# transmitter_pcb.net
KiCad netlist of a schematic drawn in EAGLE
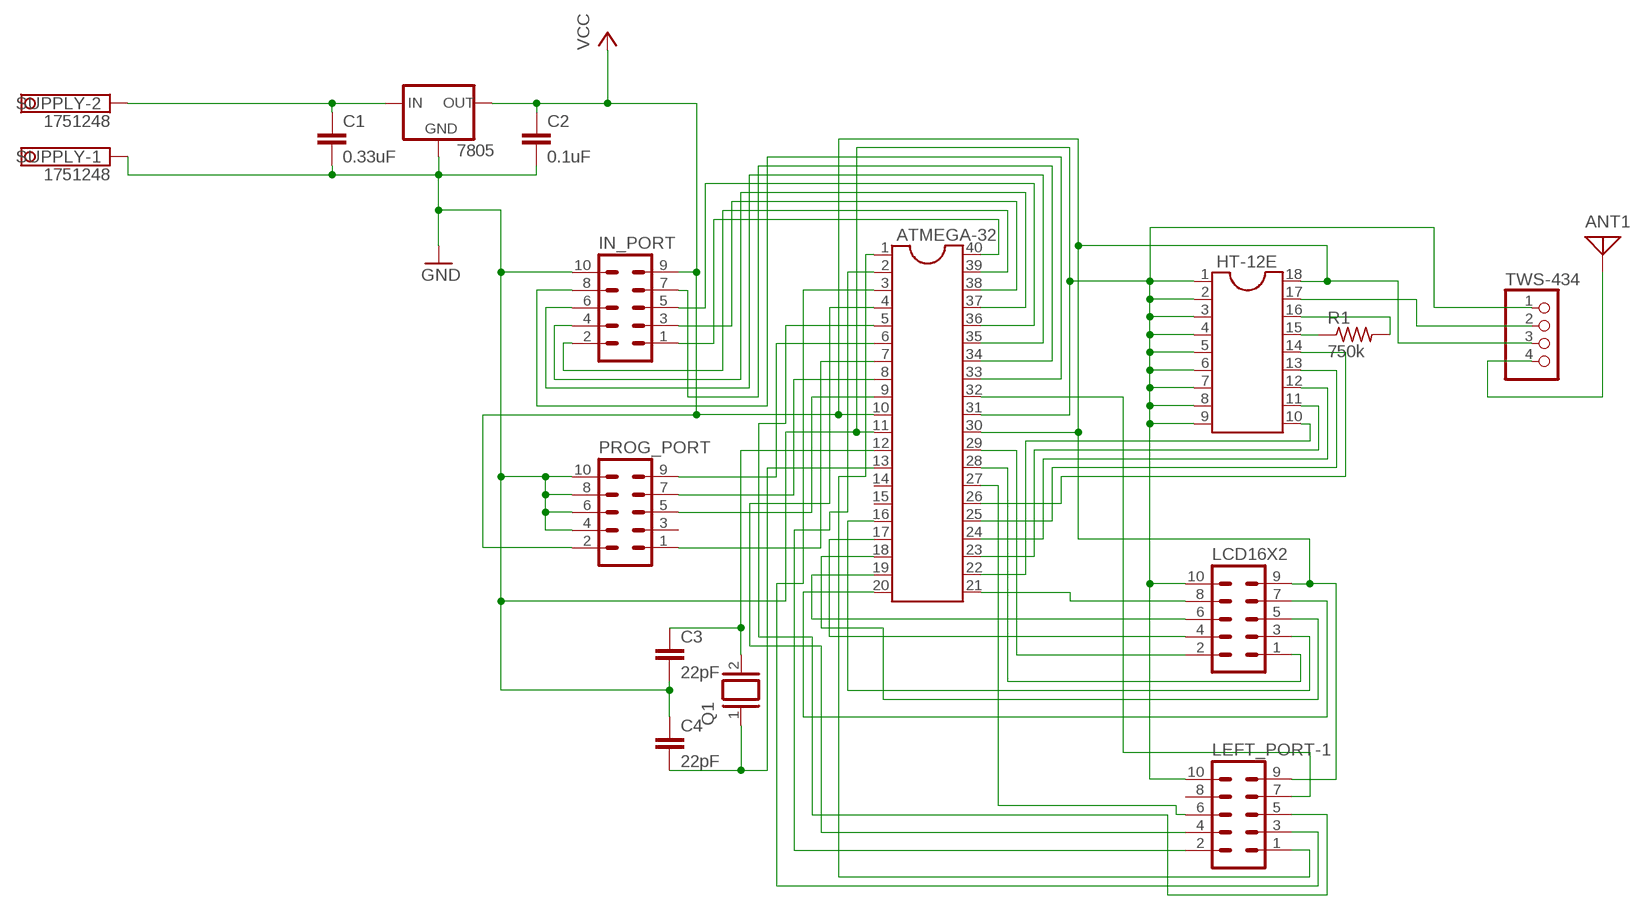
[diagram p0: schematic, sheet 1]

(export (version "E")
  (design (tool "Eeschema 10.0.6"))
  (components
    (comp (ref "7805")
      (value "78XXS")
      (footprint "eagle-import:78XXS")
      (libsource (lib "eagle-import") (part "78XXS"))
    )
    (comp (ref "ANT1")
      (value "ANTENNA")
      (footprint "eagle-import:PAD-01")
      (libsource (lib "eagle-import") (part "ANTENNA"))
    )
    (comp (ref "ATMEGA-32")
      (value "DIL40")
      (footprint "eagle-import:DIL40")
      (libsource (lib "eagle-import") (part "DIL40"))
    )
    (comp (ref "C1")
      (value "0.33uF")
      (footprint "eagle-import:C2.5-2")
      (libsource (lib "eagle-import") (part "C2.5/2"))
    )
    (comp (ref "C2")
      (value "0.1uF")
      (footprint "eagle-import:C2.5-2")
      (libsource (lib "eagle-import") (part "C2.5/2"))
    )
    (comp (ref "C3")
      (value "22pF")
      (footprint "eagle-import:C2.5-2")
      (libsource (lib "eagle-import") (part "C2.5/2"))
    )
    (comp (ref "C4")
      (value "22pF")
      (footprint "eagle-import:C2.5-2")
      (libsource (lib "eagle-import") (part "C2.5/2"))
    )
    (comp (ref "HT-12E")
      (value "DIL18")
      (footprint "eagle-import:DIL18")
      (libsource (lib "eagle-import") (part "DIL18"))
    )
    (comp (ref "IN_PORT")
      (value "ML10")
      (footprint "eagle-import:ML10")
      (libsource (lib "eagle-import") (part "ML10"))
    )
    (comp (ref "LCD16X2")
      (value "ML10")
      (footprint "eagle-import:ML10")
      (libsource (lib "eagle-import") (part "ML10"))
    )
    (comp (ref "LEFT_PORT-1")
      (value "ML10")
      (footprint "eagle-import:ML10")
      (libsource (lib "eagle-import") (part "ML10"))
    )
    (comp (ref "PROG_PORT")
      (value "ML10")
      (footprint "eagle-import:ML10")
      (libsource (lib "eagle-import") (part "ML10"))
    )
    (comp (ref "Q1")
      (value "XTAL/S")
      (footprint "eagle-import:QS")
      (libsource (lib "eagle-import") (part "XTAL/S"))
    )
    (comp (ref "R1")
      (value "750k")
      (footprint "eagle-import:0204_5")
      (libsource (lib "eagle-import") (part "R-US_0204/5"))
    )
    (comp (ref "SUPPLY")
      (value "1751248")
      (footprint "eagle-import:1751248")
      (libsource (lib "eagle-import") (part "1751248"))
    )
    (comp (ref "TWS-434")
      (value "PINHD-1X4")
      (footprint "eagle-import:1X04")
      (libsource (lib "eagle-import") (part "PINHD-1X4"))
    )
  )
  (nets
    (net (code "1") (name "GND") (class "Default")
      (node (ref "7805") (pin "GND") (pinfunction "GND_GND") (pintype "input"))
      (node (ref "ATMEGA-32") (pin "11") (pinfunction "11_11") (pintype "passive"))
      (node (ref "ATMEGA-32") (pin "31") (pinfunction "31_31") (pintype "passive"))
      (node (ref "C1") (pin "2") (pinfunction "2_2") (pintype "passive"))
      (node (ref "C2") (pin "2") (pinfunction "2_2") (pintype "passive"))
      (node (ref "C3") (pin "2") (pinfunction "2_2") (pintype "passive"))
      (node (ref "C4") (pin "1") (pinfunction "1_1") (pintype "passive"))
      (node (ref "HT-12E") (pin "1") (pinfunction "1_1") (pintype "passive"))
      (node (ref "HT-12E") (pin "2") (pinfunction "2_2") (pintype "passive"))
      (node (ref "HT-12E") (pin "3") (pinfunction "3_3") (pintype "passive"))
      (node (ref "HT-12E") (pin "4") (pinfunction "4_4") (pintype "passive"))
      (node (ref "HT-12E") (pin "5") (pinfunction "5_5") (pintype "passive"))
      (node (ref "HT-12E") (pin "6") (pinfunction "6_6") (pintype "passive"))
      (node (ref "HT-12E") (pin "7") (pinfunction "7_7") (pintype "passive"))
      (node (ref "HT-12E") (pin "8") (pinfunction "8_8") (pintype "passive"))
      (node (ref "HT-12E") (pin "9") (pinfunction "9_9") (pintype "passive"))
      (node (ref "IN_PORT") (pin "10") (pinfunction "10_10") (pintype "passive"))
      (node (ref "LCD16X2") (pin "10") (pinfunction "10_10") (pintype "passive"))
      (node (ref "LEFT_PORT-1") (pin "10") (pinfunction "10_10") (pintype "passive"))
      (node (ref "PROG_PORT") (pin "10") (pinfunction "10_10") (pintype "passive"))
      (node (ref "PROG_PORT") (pin "4") (pinfunction "4_4") (pintype "passive"))
      (node (ref "PROG_PORT") (pin "6") (pinfunction "6_6") (pintype "passive"))
      (node (ref "PROG_PORT") (pin "8") (pinfunction "8_8") (pintype "passive"))
      (node (ref "SUPPLY") (pin "1") (pinfunction "K_1") (pintype "passive"))
      (node (ref "TWS-434") (pin "1") (pinfunction "1_1") (pintype "passive"))
    )
    (net (code "2") (name "Net-(ANT1-Pad1)") (class "Default")
      (node (ref "ANT1") (pin "1") (pinfunction "1_1") (pintype "output"))
      (node (ref "TWS-434") (pin "4") (pinfunction "4_4") (pintype "passive"))
    )
    (net (code "3") (name "Net-(ATMEGA-32-Pad1)") (class "Default")
      (node (ref "ATMEGA-32") (pin "1") (pinfunction "1_1") (pintype "passive"))
      (node (ref "LEFT_PORT-1") (pin "1") (pinfunction "1_1") (pintype "passive"))
    )
    (net (code "4") (name "Net-(ATMEGA-32-Pad2)") (class "Default")
      (node (ref "ATMEGA-32") (pin "2") (pinfunction "2_2") (pintype "passive"))
      (node (ref "LEFT_PORT-1") (pin "2") (pinfunction "2_2") (pintype "passive"))
    )
    (net (code "5") (name "Net-(ATMEGA-32-Pad3)") (class "Default")
      (node (ref "ATMEGA-32") (pin "3") (pinfunction "3_3") (pintype "passive"))
      (node (ref "LEFT_PORT-1") (pin "3") (pinfunction "3_3") (pintype "passive"))
    )
    (net (code "6") (name "Net-(ATMEGA-32-Pad4)") (class "Default")
      (node (ref "ATMEGA-32") (pin "4") (pinfunction "4_4") (pintype "passive"))
      (node (ref "LEFT_PORT-1") (pin "4") (pinfunction "4_4") (pintype "passive"))
    )
    (net (code "7") (name "Net-(ATMEGA-32-Pad5)") (class "Default")
      (node (ref "ATMEGA-32") (pin "5") (pinfunction "5_5") (pintype "passive"))
      (node (ref "LEFT_PORT-1") (pin "5") (pinfunction "5_5") (pintype "passive"))
    )
    (net (code "8") (name "Net-(ATMEGA-32-Pad6)") (class "Default")
      (node (ref "ATMEGA-32") (pin "6") (pinfunction "6_6") (pintype "passive"))
      (node (ref "PROG_PORT") (pin "9") (pinfunction "9_9") (pintype "passive"))
    )
    (net (code "9") (name "Net-(ATMEGA-32-Pad7)") (class "Default")
      (node (ref "ATMEGA-32") (pin "7") (pinfunction "7_7") (pintype "passive"))
      (node (ref "PROG_PORT") (pin "1") (pinfunction "1_1") (pintype "passive"))
    )
    (net (code "10") (name "Net-(ATMEGA-32-Pad8)") (class "Default")
      (node (ref "ATMEGA-32") (pin "8") (pinfunction "8_8") (pintype "passive"))
      (node (ref "PROG_PORT") (pin "7") (pinfunction "7_7") (pintype "passive"))
    )
    (net (code "11") (name "Net-(ATMEGA-32-Pad9)") (class "Default")
      (node (ref "ATMEGA-32") (pin "9") (pinfunction "9_9") (pintype "passive"))
      (node (ref "PROG_PORT") (pin "5") (pinfunction "5_5") (pintype "passive"))
    )
    (net (code "12") (name "Net-(ATMEGA-32-Pad12)") (class "Default")
      (node (ref "ATMEGA-32") (pin "12") (pinfunction "12_12") (pintype "passive"))
      (node (ref "C3") (pin "1") (pinfunction "1_1") (pintype "passive"))
      (node (ref "Q1") (pin "2") (pinfunction "2_2") (pintype "passive"))
    )
    (net (code "13") (name "Net-(ATMEGA-32-Pad13)") (class "Default")
      (node (ref "ATMEGA-32") (pin "13") (pinfunction "13_13") (pintype "passive"))
      (node (ref "C4") (pin "2") (pinfunction "2_2") (pintype "passive"))
      (node (ref "Q1") (pin "1") (pinfunction "1_1") (pintype "passive"))
    )
    (net (code "14") (name "Net-(ATMEGA-32-Pad16)") (class "Default")
      (node (ref "ATMEGA-32") (pin "16") (pinfunction "16_16") (pintype "passive"))
      (node (ref "LCD16X2") (pin "3") (pinfunction "3_3") (pintype "passive"))
    )
    (net (code "15") (name "Net-(ATMEGA-32-Pad17)") (class "Default")
      (node (ref "ATMEGA-32") (pin "17") (pinfunction "17_17") (pintype "passive"))
      (node (ref "LCD16X2") (pin "4") (pinfunction "4_4") (pintype "passive"))
    )
    (net (code "16") (name "Net-(ATMEGA-32-Pad18)") (class "Default")
      (node (ref "ATMEGA-32") (pin "18") (pinfunction "18_18") (pintype "passive"))
      (node (ref "LCD16X2") (pin "5") (pinfunction "5_5") (pintype "passive"))
    )
    (net (code "17") (name "Net-(ATMEGA-32-Pad19)") (class "Default")
      (node (ref "ATMEGA-32") (pin "19") (pinfunction "19_19") (pintype "passive"))
      (node (ref "LCD16X2") (pin "6") (pinfunction "6_6") (pintype "passive"))
    )
    (net (code "18") (name "Net-(ATMEGA-32-Pad20)") (class "Default")
      (node (ref "ATMEGA-32") (pin "20") (pinfunction "20_20") (pintype "passive"))
      (node (ref "LCD16X2") (pin "7") (pinfunction "7_7") (pintype "passive"))
    )
    (net (code "19") (name "Net-(ATMEGA-32-Pad21)") (class "Default")
      (node (ref "ATMEGA-32") (pin "21") (pinfunction "21_21") (pintype "passive"))
      (node (ref "LCD16X2") (pin "8") (pinfunction "8_8") (pintype "passive"))
    )
    (net (code "20") (name "Net-(ATMEGA-32-Pad22)") (class "Default")
      (node (ref "ATMEGA-32") (pin "22") (pinfunction "22_22") (pintype "passive"))
      (node (ref "HT-12E") (pin "10") (pinfunction "10_10") (pintype "passive"))
    )
    (net (code "21") (name "Net-(ATMEGA-32-Pad23)") (class "Default")
      (node (ref "ATMEGA-32") (pin "23") (pinfunction "23_23") (pintype "passive"))
      (node (ref "HT-12E") (pin "11") (pinfunction "11_11") (pintype "passive"))
    )
    (net (code "22") (name "Net-(ATMEGA-32-Pad24)") (class "Default")
      (node (ref "ATMEGA-32") (pin "24") (pinfunction "24_24") (pintype "passive"))
      (node (ref "HT-12E") (pin "12") (pinfunction "12_12") (pintype "passive"))
    )
    (net (code "23") (name "Net-(ATMEGA-32-Pad25)") (class "Default")
      (node (ref "ATMEGA-32") (pin "25") (pinfunction "25_25") (pintype "passive"))
      (node (ref "HT-12E") (pin "13") (pinfunction "13_13") (pintype "passive"))
    )
    (net (code "24") (name "Net-(ATMEGA-32-Pad26)") (class "Default")
      (node (ref "ATMEGA-32") (pin "26") (pinfunction "26_26") (pintype "passive"))
      (node (ref "HT-12E") (pin "14") (pinfunction "14_14") (pintype "passive"))
    )
    (net (code "25") (name "Net-(ATMEGA-32-Pad27)") (class "Default")
      (node (ref "ATMEGA-32") (pin "27") (pinfunction "27_27") (pintype "passive"))
      (node (ref "LEFT_PORT-1") (pin "6") (pinfunction "6_6") (pintype "passive"))
    )
    (net (code "26") (name "Net-(ATMEGA-32-Pad28)") (class "Default")
      (node (ref "ATMEGA-32") (pin "28") (pinfunction "28_28") (pintype "passive"))
      (node (ref "LCD16X2") (pin "1") (pinfunction "1_1") (pintype "passive"))
    )
    (net (code "27") (name "Net-(ATMEGA-32-Pad29)") (class "Default")
      (node (ref "ATMEGA-32") (pin "29") (pinfunction "29_29") (pintype "passive"))
      (node (ref "LCD16X2") (pin "2") (pinfunction "2_2") (pintype "passive"))
    )
    (net (code "28") (name "Net-(ATMEGA-32-Pad32)") (class "Default")
      (node (ref "ATMEGA-32") (pin "32") (pinfunction "32_32") (pintype "passive"))
      (node (ref "LEFT_PORT-1") (pin "7") (pinfunction "7_7") (pintype "passive"))
    )
    (net (code "29") (name "Net-(ATMEGA-32-Pad33)") (class "Default")
      (node (ref "ATMEGA-32") (pin "33") (pinfunction "33_33") (pintype "passive"))
      (node (ref "IN_PORT") (pin "8") (pinfunction "8_8") (pintype "passive"))
    )
    (net (code "30") (name "Net-(ATMEGA-32-Pad34)") (class "Default")
      (node (ref "ATMEGA-32") (pin "34") (pinfunction "34_34") (pintype "passive"))
      (node (ref "IN_PORT") (pin "7") (pinfunction "7_7") (pintype "passive"))
    )
    (net (code "31") (name "Net-(ATMEGA-32-Pad35)") (class "Default")
      (node (ref "ATMEGA-32") (pin "35") (pinfunction "35_35") (pintype "passive"))
      (node (ref "IN_PORT") (pin "6") (pinfunction "6_6") (pintype "passive"))
    )
    (net (code "32") (name "Net-(ATMEGA-32-Pad36)") (class "Default")
      (node (ref "ATMEGA-32") (pin "36") (pinfunction "36_36") (pintype "passive"))
      (node (ref "IN_PORT") (pin "5") (pinfunction "5_5") (pintype "passive"))
    )
    (net (code "33") (name "Net-(ATMEGA-32-Pad37)") (class "Default")
      (node (ref "ATMEGA-32") (pin "37") (pinfunction "37_37") (pintype "passive"))
      (node (ref "IN_PORT") (pin "4") (pinfunction "4_4") (pintype "passive"))
    )
    (net (code "34") (name "Net-(ATMEGA-32-Pad38)") (class "Default")
      (node (ref "ATMEGA-32") (pin "38") (pinfunction "38_38") (pintype "passive"))
      (node (ref "IN_PORT") (pin "3") (pinfunction "3_3") (pintype "passive"))
    )
    (net (code "35") (name "Net-(ATMEGA-32-Pad39)") (class "Default")
      (node (ref "ATMEGA-32") (pin "39") (pinfunction "39_39") (pintype "passive"))
      (node (ref "IN_PORT") (pin "2") (pinfunction "2_2") (pintype "passive"))
    )
    (net (code "36") (name "Net-(ATMEGA-32-Pad40)") (class "Default")
      (node (ref "ATMEGA-32") (pin "40") (pinfunction "40_40") (pintype "passive"))
      (node (ref "IN_PORT") (pin "1") (pinfunction "1_1") (pintype "passive"))
    )
    (net (code "37") (name "Net-(HT-12E-Pad15)") (class "Default")
      (node (ref "HT-12E") (pin "15") (pinfunction "15_15") (pintype "passive"))
      (node (ref "R1") (pin "1") (pinfunction "1_1") (pintype "passive"))
    )
    (net (code "38") (name "Net-(HT-12E-Pad16)") (class "Default")
      (node (ref "HT-12E") (pin "16") (pinfunction "16_16") (pintype "passive"))
      (node (ref "R1") (pin "2") (pinfunction "2_2") (pintype "passive"))
    )
    (net (code "39") (name "Net-(HT-12E-Pad17)") (class "Default")
      (node (ref "HT-12E") (pin "17") (pinfunction "17_17") (pintype "passive"))
      (node (ref "TWS-434") (pin "2") (pinfunction "2_2") (pintype "passive"))
    )
    (net (code "40") (name "Net-(SUPPLYB-K)") (class "Default")
      (node (ref "7805") (pin "IN") (pinfunction "IN_IN") (pintype "input"))
      (node (ref "C1") (pin "1") (pinfunction "1_1") (pintype "passive"))
      (node (ref "SUPPLY") (pin "2") (pinfunction "K_2") (pintype "passive"))
    )
    (net (code "41") (name "VCC") (class "Default")
      (node (ref "7805") (pin "OUT") (pinfunction "OUT_OUT") (pintype "passive"))
      (node (ref "ATMEGA-32") (pin "10") (pinfunction "10_10") (pintype "passive"))
      (node (ref "ATMEGA-32") (pin "30") (pinfunction "30_30") (pintype "passive"))
      (node (ref "C2") (pin "1") (pinfunction "1_1") (pintype "passive"))
      (node (ref "HT-12E") (pin "18") (pinfunction "18_18") (pintype "passive"))
      (node (ref "IN_PORT") (pin "9") (pinfunction "9_9") (pintype "passive"))
      (node (ref "LCD16X2") (pin "9") (pinfunction "9_9") (pintype "passive"))
      (node (ref "LEFT_PORT-1") (pin "9") (pinfunction "9_9") (pintype "passive"))
      (node (ref "PROG_PORT") (pin "2") (pinfunction "2_2") (pintype "passive"))
      (node (ref "TWS-434") (pin "3") (pinfunction "3_3") (pintype "passive"))
    )
    (net (code "42") (name "unconnected-(ATMEGA-32-Pad14)") (class "Default")
      (node (ref "ATMEGA-32") (pin "14") (pinfunction "14_14") (pintype "passive"))
    )
    (net (code "43") (name "unconnected-(ATMEGA-32-Pad15)") (class "Default")
      (node (ref "ATMEGA-32") (pin "15") (pinfunction "15_15") (pintype "passive"))
    )
    (net (code "44") (name "unconnected-(LEFT_PORT-1-Pad8)") (class "Default")
      (node (ref "LEFT_PORT-1") (pin "8") (pinfunction "8_8") (pintype "passive"))
    )
    (net (code "45") (name "unconnected-(PROG_PORT-Pad3)") (class "Default")
      (node (ref "PROG_PORT") (pin "3") (pinfunction "3_3") (pintype "passive"))
    )
  )
)
